# Power.net
KiCad netlist of a schematic drawn in Altium Designer
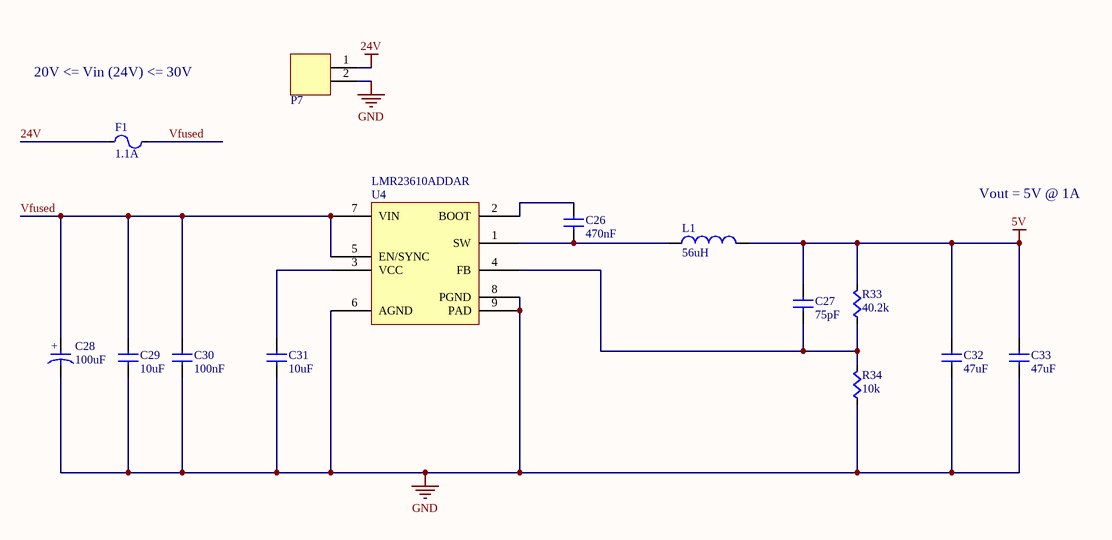
[diagram p0: Power.SchDoc]

(export (version "E")
  (design (tool "Eeschema 10.0.6"))
  (components
    (comp (ref "C26")
      (value "470nF")
      (footprint "CAPC0603")
      (fields (field (name "Comment") "Cap"))
      (libsource (lib "Passives") (part "Cap"))
    )
    (comp (ref "C27")
      (value "75pF")
      (footprint "CAPC0603")
      (fields (field (name "Comment") "Cap"))
      (libsource (lib "Passives") (part "Cap"))
    )
    (comp (ref "C28")
      (value "100uF")
      (footprint "EEHZA1H101P")
      (description "CAP ALUM POLY HYB 100UF 50V SMD")
      (fields (field (name "VOLTAGE") "50V") (field (name "TOLERANCE") "20%"))
      (libsource (lib "SubjuGator8") (part "EEHZA1H101P"))
    )
    (comp (ref "C29")
      (value "10uF")
      (footprint "CAP1210")
      (fields (field (name "Comment") "Cap"))
      (libsource (lib "Passives") (part "Cap"))
    )
    (comp (ref "C30")
      (value "100nF")
      (footprint "CAPC0603")
      (fields (field (name "Comment") "Cap"))
      (libsource (lib "Passives") (part "Cap"))
    )
    (comp (ref "C31")
      (value "10uF")
      (footprint "CAPC0603")
      (fields (field (name "Comment") "Cap"))
      (libsource (lib "Passives") (part "Cap"))
    )
    (comp (ref "C32")
      (value "47uF")
      (footprint "CAP1210")
      (fields (field (name "Comment") "Cap"))
      (libsource (lib "SubjuGator8") (part "Cap"))
    )
    (comp (ref "C33")
      (value "47uF")
      (footprint "CAP1210")
      (fields (field (name "Comment") "Cap"))
      (libsource (lib "SubjuGator8") (part "Cap"))
    )
    (comp (ref "F1")
      (value "1.1A")
      (footprint "PTC7451X11N")
      (fields (field (name "Comment") "PTC Fuse"))
      (libsource (lib "SubjuGator8") (part "PTC_Fuse"))
    )
    (comp (ref "L1")
      (value "56uH")
      (footprint "MSS1048-563MLB")
      (description "FIXED IND 56UH 1.7A 126 MOHM")
      (fields (field (name "Comment") "MSS1048-563MLB"))
      (libsource (lib "SubjuGator8") (part "MSS1048-563MLB"))
    )
    (comp (ref "P7")
      (value "2-pin Vert Sherlock")
      (footprint "MOLEX-HDR-1X2-SHERLOCK-VERT")
      (libsource (lib "SubjuGator8") (part "MOLEX-HDR-1x2-SHERLOCK_VERT"))
    )
    (comp (ref "R33")
      (value "40.2k")
      (footprint "RES0603")
      (fields (field (name "Comment") "Res"))
      (libsource (lib "SubjuGator8") (part "Res"))
    )
    (comp (ref "R34")
      (value "10k")
      (footprint "RES0603")
      (fields (field (name "Comment") "Res"))
      (libsource (lib "SubjuGator8") (part "Res"))
    )
    (comp (ref "U4")
      (value "LMR23610ADDAR")
      (footprint "LMR23610ADDAR")
      (description "IC REG BUCK ADJ 1A SYNC 8SOPWRPD")
      (libsource (lib "SubjuGator8") (part "LMR23610ADDAR"))
    )
  )
  (nets
    (net (code "1") (name "/Vfused") (class "Default")
      (node (ref "C28") (pin "1") (pinfunction "1_1") (pintype "passive"))
      (node (ref "C29") (pin "1") (pinfunction "A_1") (pintype "passive"))
      (node (ref "C30") (pin "1") (pinfunction "A_1") (pintype "passive"))
      (node (ref "F1") (pin "2") (pinfunction "B_2") (pintype "passive"))
      (node (ref "U4") (pin "5") (pinfunction "EN/SYNC_5") (pintype "passive"))
      (node (ref "U4") (pin "7") (pinfunction "VIN_7") (pintype "passive"))
    )
    (net (code "2") (name "5V") (class "Default")
      (node (ref "C27") (pin "1") (pinfunction "A_1") (pintype "passive"))
      (node (ref "C32") (pin "1") (pinfunction "A_1") (pintype "passive"))
      (node (ref "C33") (pin "1") (pinfunction "A_1") (pintype "passive"))
      (node (ref "L1") (pin "2") (pinfunction "2_2") (pintype "passive"))
      (node (ref "R33") (pin "1") (pinfunction "A_1") (pintype "passive"))
    )
    (net (code "3") (name "24V") (class "Default")
      (node (ref "F1") (pin "1") (pinfunction "A_1") (pintype "passive"))
      (node (ref "P7") (pin "1") (pinfunction "1_1") (pintype "passive"))
    )
    (net (code "4") (name "GND") (class "Default")
      (node (ref "C28") (pin "2") (pinfunction "2_2") (pintype "passive"))
      (node (ref "C29") (pin "2") (pinfunction "B_2") (pintype "passive"))
      (node (ref "C30") (pin "2") (pinfunction "B_2") (pintype "passive"))
      (node (ref "C31") (pin "2") (pinfunction "B_2") (pintype "passive"))
      (node (ref "C32") (pin "2") (pinfunction "B_2") (pintype "passive"))
      (node (ref "C33") (pin "2") (pinfunction "B_2") (pintype "passive"))
      (node (ref "P7") (pin "2") (pinfunction "2_2") (pintype "passive"))
      (node (ref "R34") (pin "2") (pinfunction "B_2") (pintype "passive"))
      (node (ref "U4") (pin "6") (pinfunction "AGND_6") (pintype "passive"))
      (node (ref "U4") (pin "8") (pinfunction "PGND_8") (pintype "passive"))
      (node (ref "U4") (pin "9") (pinfunction "PAD_9") (pintype "passive"))
    )
    (net (code "5") (name "Net-(C26-A)") (class "Default")
      (node (ref "C26") (pin "1") (pinfunction "A_1") (pintype "passive"))
      (node (ref "U4") (pin "2") (pinfunction "BOOT_2") (pintype "passive"))
    )
    (net (code "6") (name "Net-(C26-B)") (class "Default")
      (node (ref "C26") (pin "2") (pinfunction "B_2") (pintype "passive"))
      (node (ref "L1") (pin "1") (pinfunction "1_1") (pintype "passive"))
      (node (ref "U4") (pin "1") (pinfunction "SW_1") (pintype "passive"))
    )
    (net (code "7") (name "Net-(C27-B)") (class "Default")
      (node (ref "C27") (pin "2") (pinfunction "B_2") (pintype "passive"))
      (node (ref "R33") (pin "2") (pinfunction "B_2") (pintype "passive"))
      (node (ref "R34") (pin "1") (pinfunction "A_1") (pintype "passive"))
      (node (ref "U4") (pin "4") (pinfunction "FB_4") (pintype "passive"))
    )
    (net (code "8") (name "Net-(C31-A)") (class "Default")
      (node (ref "C31") (pin "1") (pinfunction "A_1") (pintype "passive"))
      (node (ref "U4") (pin "3") (pinfunction "VCC_3") (pintype "passive"))
    )
  )
)
